# SVPXFMC_Carrier_3U.net
KiCad netlist of a schematic drawn in Altium Designer
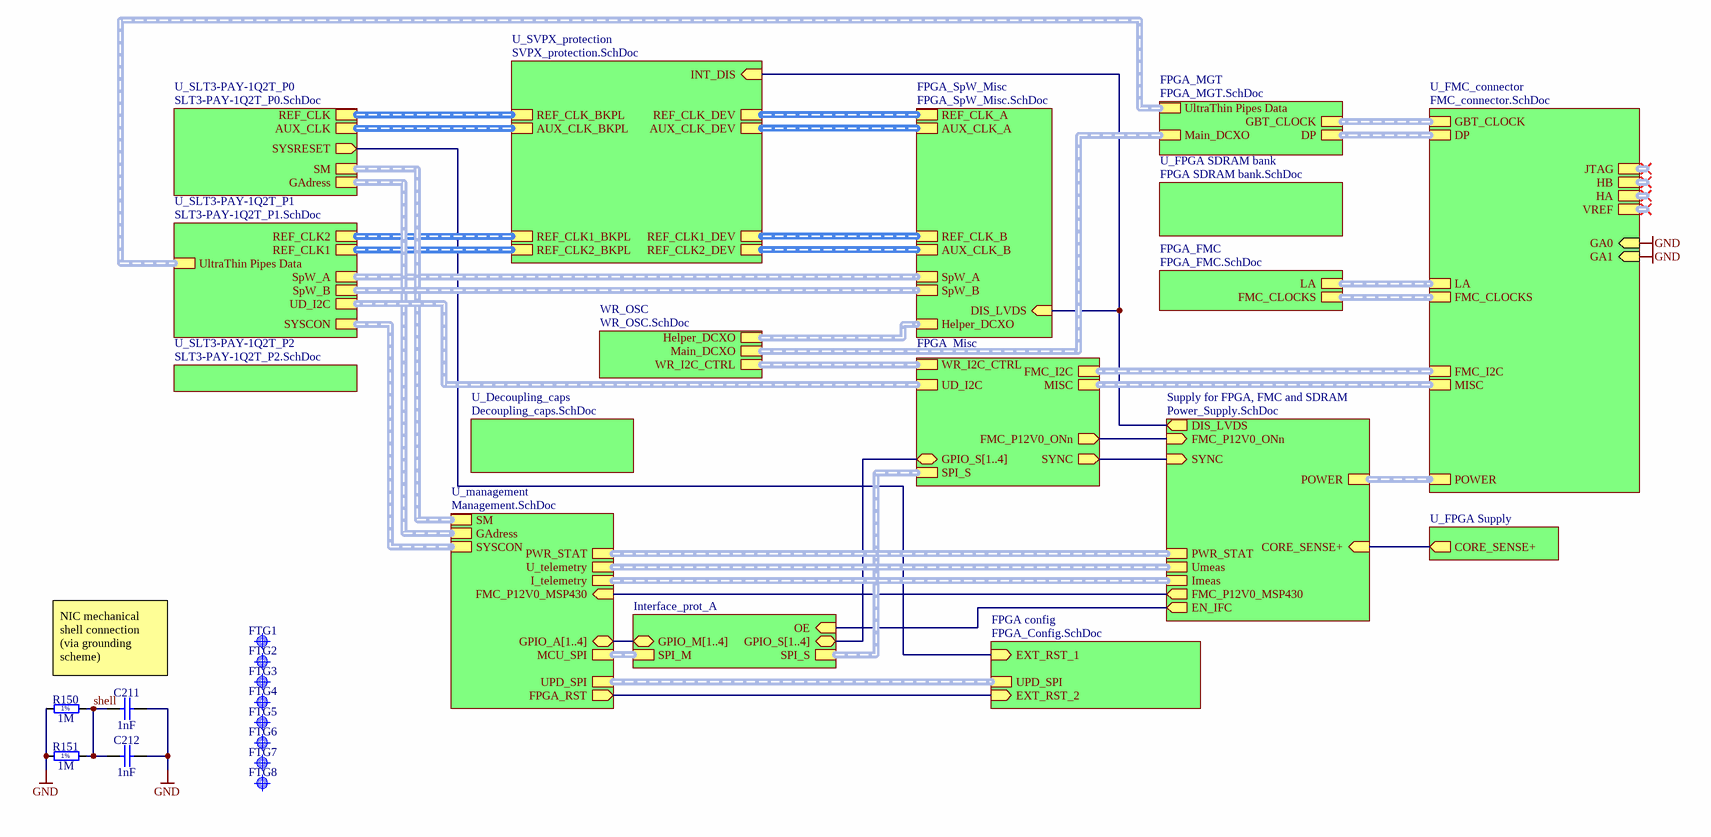
[diagram p0: SVPXFMC_Carrier_3U.SchDoc]

(export (version "E")
  (design (tool "Eeschema 10.0.6"))
  (components
    (comp (ref "C211")
      (value "1nF")
      (footprint "CAPC1005X55N")
      (description "Non-polarised capacitor")
      (fields
        (field (name "PART NUMBER") "CC0402_1NF_50V_10%_X7R")
        (field (name "VOLTAGE") "50V")
        (field (name "AUTHOR") "CERN DEM JLC")
      )
      (libsource (lib "Capacitors") (part "Capacitor - non polarized"))
    )
    (comp (ref "C212")
      (value "1nF")
      (footprint "CAPC1005X55N")
      (description "Non-polarised capacitor")
      (fields
        (field (name "PART NUMBER") "CC0402_1NF_50V_10%_X7R")
        (field (name "VOLTAGE") "50V")
        (field (name "AUTHOR") "CERN DEM JLC")
      )
      (libsource (lib "Capacitors") (part "Capacitor - non polarized"))
    )
    (comp (ref "FTG1")
      (value "Use only in PCB")
      (footprint "FIDUCIAL_TOP_C100-200")
      (description "Fiducial Target")
      (fields (field (name "PART NUMBER") "FIDUCIAL_TARGET_C100-200") (field (name "AUTHOR") "CERN DEM JLC"))
      (libsource (lib "Eletro-mechanical") (part "Fiducial Target"))
    )
    (comp (ref "FTG2")
      (value "Use only in PCB")
      (footprint "FIDUCIAL_TOP_C100-200")
      (description "Fiducial Target")
      (fields (field (name "PART NUMBER") "FIDUCIAL_TARGET_C100-200") (field (name "AUTHOR") "CERN DEM JLC"))
      (libsource (lib "Eletro-mechanical") (part "Fiducial Target"))
    )
    (comp (ref "FTG3")
      (value "Use only in PCB")
      (footprint "FIDUCIAL_TOP_C100-200")
      (description "Fiducial Target")
      (fields (field (name "PART NUMBER") "FIDUCIAL_TARGET_C100-200") (field (name "AUTHOR") "CERN DEM JLC"))
      (libsource (lib "Eletro-mechanical") (part "Fiducial Target"))
    )
    (comp (ref "FTG4")
      (value "Use only in PCB")
      (footprint "FIDUCIAL_TOP_C100-200")
      (description "Fiducial Target")
      (fields (field (name "PART NUMBER") "FIDUCIAL_TARGET_C100-200") (field (name "AUTHOR") "CERN DEM JLC"))
      (libsource (lib "Eletro-mechanical") (part "Fiducial Target"))
    )
    (comp (ref "FTG5")
      (value "Use only in PCB")
      (footprint "FIDUCIAL_TOP_C100-200")
      (description "Fiducial Target")
      (fields (field (name "PART NUMBER") "FIDUCIAL_TARGET_C100-200") (field (name "AUTHOR") "CERN DEM JLC"))
      (libsource (lib "Eletro-mechanical") (part "Fiducial Target"))
    )
    (comp (ref "FTG6")
      (value "Use only in PCB")
      (footprint "FIDUCIAL_TOP_C100-200")
      (description "Fiducial Target")
      (fields (field (name "PART NUMBER") "FIDUCIAL_TARGET_C100-200") (field (name "AUTHOR") "CERN DEM JLC"))
      (libsource (lib "Eletro-mechanical") (part "Fiducial Target"))
    )
    (comp (ref "FTG7")
      (value "Use only in PCB")
      (footprint "FIDUCIAL_TOP_C100-200")
      (description "Fiducial Target")
      (fields (field (name "PART NUMBER") "FIDUCIAL_TARGET_C100-200") (field (name "AUTHOR") "CERN DEM JLC"))
      (libsource (lib "Eletro-mechanical") (part "Fiducial Target"))
    )
    (comp (ref "FTG8")
      (value "Use only in PCB")
      (footprint "FIDUCIAL_TOP_C100-200")
      (description "Fiducial Target")
      (fields (field (name "PART NUMBER") "FIDUCIAL_TARGET_C100-200") (field (name "AUTHOR") "CERN DEM JLC"))
      (libsource (lib "Eletro-mechanical") (part "Fiducial Target"))
    )
    (comp (ref "R150")
      (value "1M")
      (footprint "RESC1005X40N")
      (description "Resistor - 1%")
      (fields
        (field (name "PART NUMBER") "R0402_1M_1%_0.0625W_100PPM")
        (field (name "POWER") "0.0625W")
        (field (name "AUTHOR") "CERN DEM JLC")
      )
      (libsource (lib "Resistors") (part "Resistor - 1%"))
    )
    (comp (ref "R151")
      (value "1M")
      (footprint "RESC1005X40N")
      (description "Resistor - 1%")
      (fields
        (field (name "PART NUMBER") "R0402_1M_1%_0.0625W_100PPM")
        (field (name "POWER") "0.0625W")
        (field (name "AUTHOR") "CERN DEM JLC")
      )
      (libsource (lib "Resistors") (part "Resistor - 1%"))
    )
  )
  (nets
    (net (code "46") (name "/shell") (class "Default")
      (node (ref "C211") (pin "1") (pinfunction "1_1") (pintype "passive"))
      (node (ref "C212") (pin "1") (pinfunction "1_1") (pintype "passive"))
      (node (ref "R150") (pin "2") (pinfunction "2_2") (pintype "passive"))
      (node (ref "R151") (pin "2") (pinfunction "2_2") (pintype "passive"))
    )
    (net (code "47") (name "GND") (class "Default")
      (node (ref "C211") (pin "2") (pinfunction "2_2") (pintype "passive"))
      (node (ref "C212") (pin "2") (pinfunction "2_2") (pintype "passive"))
      (node (ref "R150") (pin "1") (pinfunction "1_1") (pintype "passive"))
      (node (ref "R151") (pin "1") (pinfunction "1_1") (pintype "passive"))
    )
  )
)
